# sch_ma.net
KiCad netlist of a schematic drawn in Altium Designer
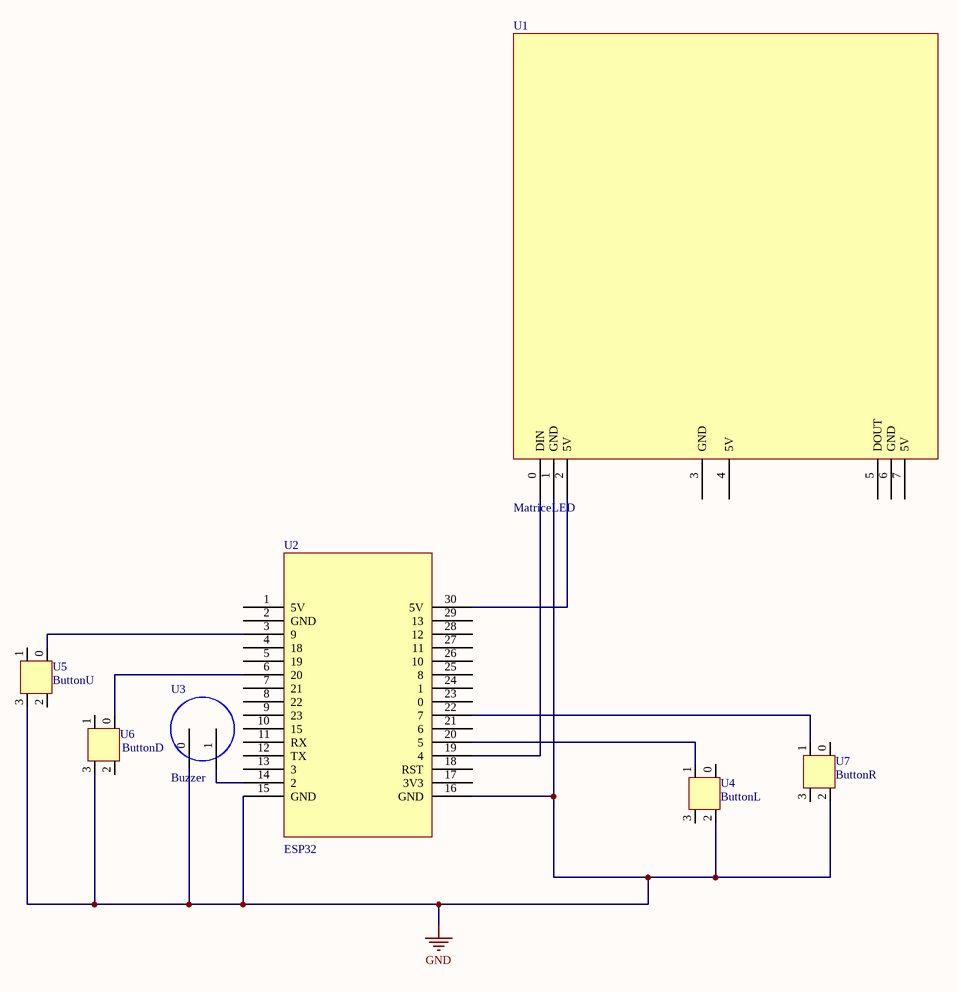
[diagram p0: schéma.SchDoc]

(export (version "E")
  (design (tool "Eeschema 10.0.6"))
  (components
    (comp (ref "U1")
      (value "MatriceLED")
      (footprint "MATRICEled")
      (libsource (lib "Schlib1") (part "MatriceLED"))
    )
    (comp (ref "U2") (value "ESP32") (footprint "ESP32") (libsource (lib "Schlib1") (part "ESP32C6")))
    (comp (ref "U3") (value "Buzzer") (footprint "BUZZER") (libsource (lib "Schlib1") (part "Buzzer")))
    (comp (ref "U4") (value "ButtonL") (footprint "BOUTON") (libsource (lib "Schlib1") (part "Button")))
    (comp (ref "U5") (value "ButtonU") (footprint "BOUTON") (libsource (lib "Schlib1") (part "Button")))
    (comp (ref "U6") (value "ButtonD") (footprint "BOUTON") (libsource (lib "Schlib1") (part "Button")))
    (comp (ref "U7") (value "ButtonR") (footprint "BOUTON") (libsource (lib "Schlib1") (part "Button")))
  )
  (nets
    (net (code "1") (name "GND") (class "Default")
      (node (ref "U1") (pin "1") (pinfunction "GND_1") (pintype "passive"))
      (node (ref "U2") (pin "15") (pinfunction "GND_15") (pintype "passive"))
      (node (ref "U2") (pin "16") (pinfunction "GND_16") (pintype "passive"))
      (node (ref "U3") (pin "0") (pinfunction "31_0") (pintype "passive"))
      (node (ref "U4") (pin "2") (pinfunction "31_2") (pintype "passive"))
      (node (ref "U5") (pin "3") (pinfunction "31_3") (pintype "passive"))
      (node (ref "U6") (pin "3") (pinfunction "31_3") (pintype "passive"))
      (node (ref "U7") (pin "2") (pinfunction "31_2") (pintype "passive"))
    )
    (net (code "2") (name "Net-(U1-5V-Pad2)") (class "Default")
      (node (ref "U1") (pin "2") (pinfunction "5V_2") (pintype "passive"))
      (node (ref "U2") (pin "30") (pinfunction "5V_30") (pintype "passive"))
    )
    (net (code "3") (name "Net-(U1-DIN)") (class "Default")
      (node (ref "U1") (pin "0") (pinfunction "DIN_0") (pintype "passive"))
      (node (ref "U2") (pin "19") (pinfunction "4_19") (pintype "passive"))
    )
    (net (code "4") (name "Net-(U2-2)") (class "Default")
      (node (ref "U2") (pin "14") (pinfunction "2_14") (pintype "passive"))
      (node (ref "U3") (pin "1") (pinfunction "31_1") (pintype "passive"))
    )
    (net (code "5") (name "Net-(U2-5)") (class "Default")
      (node (ref "U2") (pin "20") (pinfunction "5_20") (pintype "passive"))
      (node (ref "U4") (pin "1") (pinfunction "31_1") (pintype "passive"))
    )
    (net (code "6") (name "Net-(U2-7)") (class "Default")
      (node (ref "U2") (pin "22") (pinfunction "7_22") (pintype "passive"))
      (node (ref "U7") (pin "1") (pinfunction "31_1") (pintype "passive"))
    )
    (net (code "7") (name "Net-(U2-9)") (class "Default")
      (node (ref "U2") (pin "3") (pinfunction "9_3") (pintype "passive"))
      (node (ref "U5") (pin "0") (pinfunction "31_0") (pintype "passive"))
    )
    (net (code "8") (name "Net-(U2-20)") (class "Default")
      (node (ref "U2") (pin "6") (pinfunction "20_6") (pintype "passive"))
      (node (ref "U6") (pin "0") (pinfunction "31_0") (pintype "passive"))
    )
    (net (code "9") (name "unconnected-(U1-5V-Pad4)") (class "Default")
      (node (ref "U1") (pin "4") (pinfunction "5V_4") (pintype "passive"))
    )
    (net (code "10") (name "unconnected-(U1-5V-Pad7)") (class "Default")
      (node (ref "U1") (pin "7") (pinfunction "5V_7") (pintype "passive"))
    )
    (net (code "11") (name "unconnected-(U1-DOUT-Pad5)") (class "Default")
      (node (ref "U1") (pin "5") (pinfunction "DOUT_5") (pintype "passive"))
    )
    (net (code "12") (name "unconnected-(U1-GND-Pad3)") (class "Default")
      (node (ref "U1") (pin "3") (pinfunction "GND_3") (pintype "passive"))
    )
    (net (code "13") (name "unconnected-(U1-GND-Pad6)") (class "Default")
      (node (ref "U1") (pin "6") (pinfunction "GND_6") (pintype "passive"))
    )
    (net (code "14") (name "unconnected-(U2-0-Pad23)") (class "Default")
      (node (ref "U2") (pin "23") (pinfunction "0_23") (pintype "passive"))
    )
    (net (code "15") (name "unconnected-(U2-1-Pad24)") (class "Default")
      (node (ref "U2") (pin "24") (pinfunction "1_24") (pintype "passive"))
    )
    (net (code "16") (name "unconnected-(U2-3-Pad13)") (class "Default")
      (node (ref "U2") (pin "13") (pinfunction "3_13") (pintype "passive"))
    )
    (net (code "17") (name "unconnected-(U2-3V3-Pad17)") (class "Default")
      (node (ref "U2") (pin "17") (pinfunction "3V3_17") (pintype "passive"))
    )
    (net (code "18") (name "unconnected-(U2-5V-Pad1)") (class "Default")
      (node (ref "U2") (pin "1") (pinfunction "5V_1") (pintype "passive"))
    )
    (net (code "19") (name "unconnected-(U2-6-Pad21)") (class "Default")
      (node (ref "U2") (pin "21") (pinfunction "6_21") (pintype "passive"))
    )
    (net (code "20") (name "unconnected-(U2-8-Pad25)") (class "Default")
      (node (ref "U2") (pin "25") (pinfunction "8_25") (pintype "passive"))
    )
    (net (code "21") (name "unconnected-(U2-10-Pad26)") (class "Default")
      (node (ref "U2") (pin "26") (pinfunction "10_26") (pintype "passive"))
    )
    (net (code "22") (name "unconnected-(U2-11-Pad27)") (class "Default")
      (node (ref "U2") (pin "27") (pinfunction "11_27") (pintype "passive"))
    )
    (net (code "23") (name "unconnected-(U2-12-Pad28)") (class "Default")
      (node (ref "U2") (pin "28") (pinfunction "12_28") (pintype "passive"))
    )
    (net (code "24") (name "unconnected-(U2-13-Pad29)") (class "Default")
      (node (ref "U2") (pin "29") (pinfunction "13_29") (pintype "passive"))
    )
    (net (code "25") (name "unconnected-(U2-15-Pad10)") (class "Default")
      (node (ref "U2") (pin "10") (pinfunction "15_10") (pintype "passive"))
    )
    (net (code "26") (name "unconnected-(U2-18-Pad4)") (class "Default")
      (node (ref "U2") (pin "4") (pinfunction "18_4") (pintype "passive"))
    )
    (net (code "27") (name "unconnected-(U2-19-Pad5)") (class "Default")
      (node (ref "U2") (pin "5") (pinfunction "19_5") (pintype "passive"))
    )
    (net (code "28") (name "unconnected-(U2-21-Pad7)") (class "Default")
      (node (ref "U2") (pin "7") (pinfunction "21_7") (pintype "passive"))
    )
    (net (code "29") (name "unconnected-(U2-22-Pad8)") (class "Default")
      (node (ref "U2") (pin "8") (pinfunction "22_8") (pintype "passive"))
    )
    (net (code "30") (name "unconnected-(U2-23-Pad9)") (class "Default")
      (node (ref "U2") (pin "9") (pinfunction "23_9") (pintype "passive"))
    )
    (net (code "31") (name "unconnected-(U2-GND-Pad2)") (class "Default")
      (node (ref "U2") (pin "2") (pinfunction "GND_2") (pintype "passive"))
    )
    (net (code "32") (name "unconnected-(U2-RST-Pad18)") (class "Default")
      (node (ref "U2") (pin "18") (pinfunction "RST_18") (pintype "passive"))
    )
    (net (code "33") (name "unconnected-(U2-RX-Pad11)") (class "Default")
      (node (ref "U2") (pin "11") (pinfunction "RX_11") (pintype "passive"))
    )
    (net (code "34") (name "unconnected-(U2-TX-Pad12)") (class "Default")
      (node (ref "U2") (pin "12") (pinfunction "TX_12") (pintype "passive"))
    )
    (net (code "35") (name "unconnected-(U4-31-Pad0)") (class "Default")
      (node (ref "U4") (pin "0") (pinfunction "31_0") (pintype "passive"))
    )
    (net (code "36") (name "unconnected-(U4-31-Pad3)") (class "Default")
      (node (ref "U4") (pin "3") (pinfunction "31_3") (pintype "passive"))
    )
    (net (code "37") (name "unconnected-(U5-31-Pad1)") (class "Default")
      (node (ref "U5") (pin "1") (pinfunction "31_1") (pintype "passive"))
    )
    (net (code "38") (name "unconnected-(U5-31-Pad2)") (class "Default")
      (node (ref "U5") (pin "2") (pinfunction "31_2") (pintype "passive"))
    )
    (net (code "39") (name "unconnected-(U6-31-Pad1)") (class "Default")
      (node (ref "U6") (pin "1") (pinfunction "31_1") (pintype "passive"))
    )
    (net (code "40") (name "unconnected-(U6-31-Pad2)") (class "Default")
      (node (ref "U6") (pin "2") (pinfunction "31_2") (pintype "passive"))
    )
    (net (code "41") (name "unconnected-(U7-31-Pad0)") (class "Default")
      (node (ref "U7") (pin "0") (pinfunction "31_0") (pintype "passive"))
    )
    (net (code "42") (name "unconnected-(U7-31-Pad3)") (class "Default")
      (node (ref "U7") (pin "3") (pinfunction "31_3") (pintype "passive"))
    )
  )
)
